# MCU.net
KiCad netlist of a schematic drawn in Altium Designer
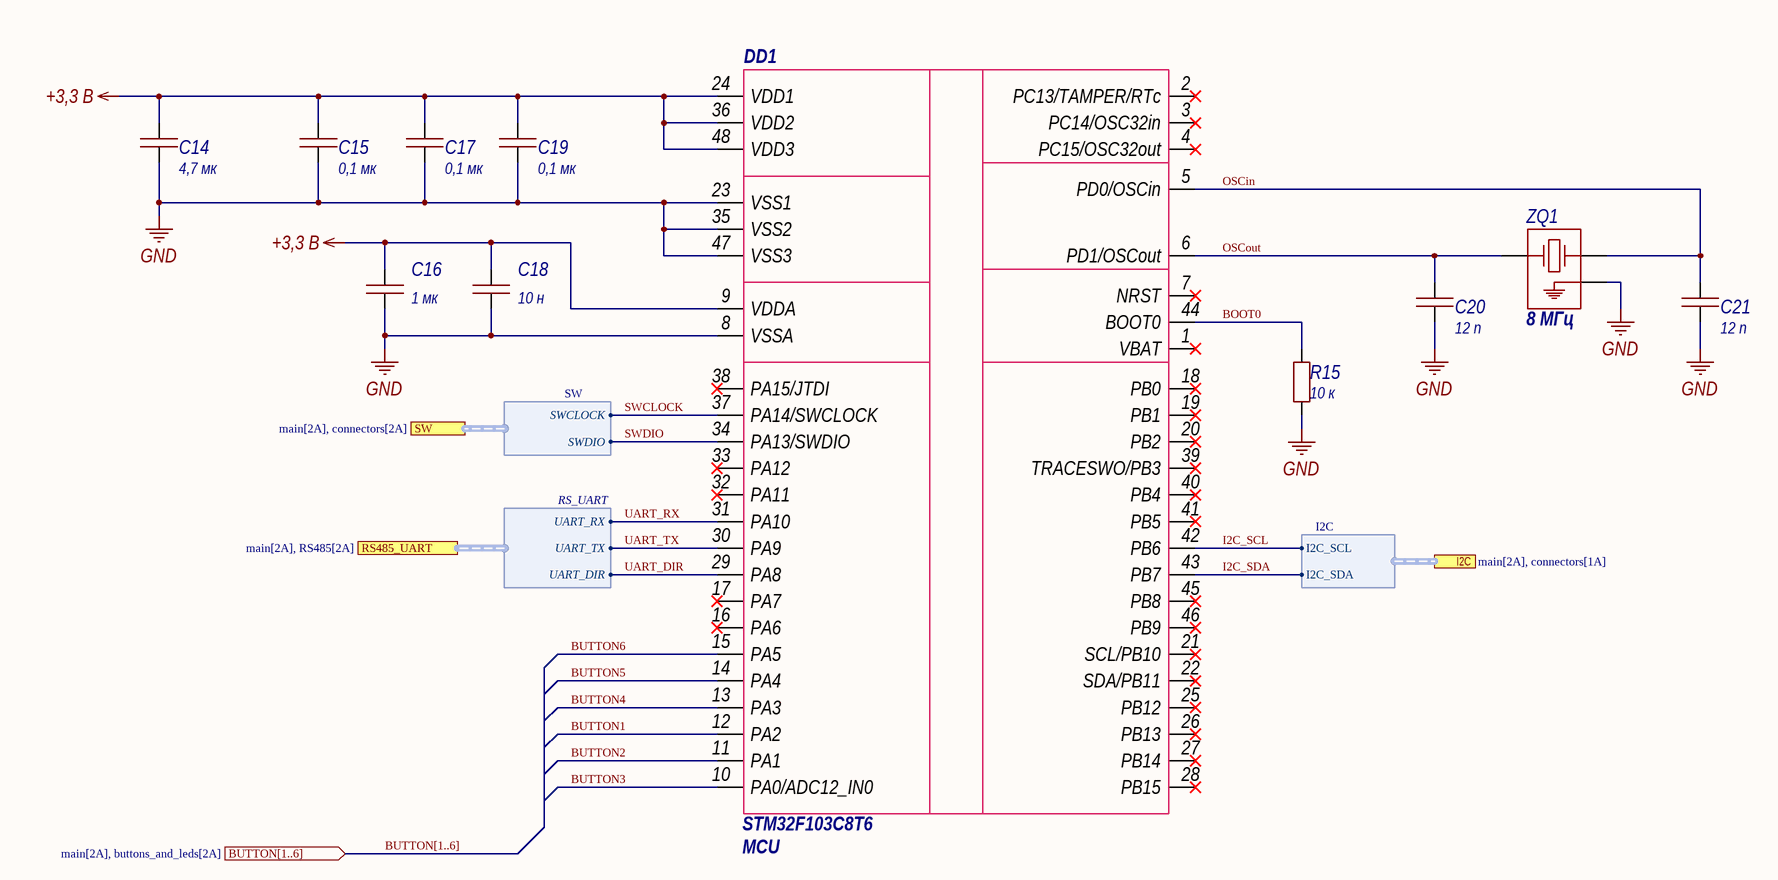
[diagram p0: MCU.SchDoc]

(export (version "E")
  (design (tool "Eeschema 10.0.6"))
  (components
    (comp (ref "C14")
      (value "4,7 мк")
      (footprint "1206C")
      (description "Конденсатор 1206C ёмкостью 4,7 мк 10%, 50 В, X7R")
      (fields (field (name "PART NUMBER") "Capacitor_4,7u_10_50V_X7R_1206C") (field (name "TOLERANCE") "10%"))
      (libsource (lib "Hydrolib") (part "Capacitor"))
    )
    (comp (ref "C15")
      (value "0,1 мк")
      (footprint "0603C")
      (description "Конденсатор 0603C ёмкостью 0,1 мк 10%, 50 В, X7R")
      (fields (field (name "PART NUMBER") "Capacitor_0,1u_10_50V_X7R_0603C") (field (name "TOLERANCE") "10%"))
      (libsource (lib "Hydrolib") (part "Capacitor"))
    )
    (comp (ref "C16")
      (value "1 мк")
      (footprint "0603C")
      (description "Конденсатор 0603C ёмкостью 1 мк 10%, 50 В, X7R")
      (fields (field (name "PART NUMBER") "Capacitor_1u_10_50V_X7R_0603C") (field (name "TOLERANCE") "10%"))
      (libsource (lib "Hydrolib") (part "Capacitor"))
    )
    (comp (ref "C17")
      (value "0,1 мк")
      (footprint "0603C")
      (description "Конденсатор 0603C ёмкостью 0,1 мк 10%, 50 В, X7R")
      (fields (field (name "PART NUMBER") "Capacitor_0,1u_10_50V_X7R_0603C") (field (name "TOLERANCE") "10%"))
      (libsource (lib "Hydrolib") (part "Capacitor"))
    )
    (comp (ref "C18")
      (value "10 н")
      (footprint "0603C")
      (description "Конденсатор 0603C ёмкостью 10 н 10%, 50 В, X7R")
      (fields (field (name "PART NUMBER") "Capacitor_10n_10_50V_X7R_0603C") (field (name "TOLERANCE") "10%"))
      (libsource (lib "Hydrolib") (part "Capacitor"))
    )
    (comp (ref "C19")
      (value "0,1 мк")
      (footprint "0603C")
      (description "Конденсатор 0603C ёмкостью 0,1 мк 10%, 50 В, X7R")
      (fields (field (name "PART NUMBER") "Capacitor_0,1u_10_50V_X7R_0603C") (field (name "TOLERANCE") "10%"))
      (libsource (lib "Hydrolib") (part "Capacitor"))
    )
    (comp (ref "C20")
      (value "12 п")
      (footprint "0603C")
      (description "Конденсатор 12п")
      (fields (field (name "PART NUMBER") "Capacitor"))
      (libsource (lib "Hydrolib") (part "Capacitor"))
    )
    (comp (ref "C21")
      (value "12 п")
      (footprint "0603C")
      (description "Конденсатор 12п")
      (fields (field (name "PART NUMBER") "Capacitor"))
      (libsource (lib "Hydrolib") (part "Capacitor"))
    )
    (comp (ref "DD1")
      (value "STM32F103C8T6")
      (footprint "LQFP48")
      (description "Микроконтроллер")
      (fields (field (name "MANUFACTURER") "ST Microelectronics") (field (name "VALUE1") "MCU"))
      (libsource (lib "Hydrolib") (part "STM32F103C8T6"))
    )
    (comp (ref "R15")
      (value "10 к")
      (footprint "0603R")
      (description "Резистор номиналом 10 кОм 1%")
      (fields (field (name "PART NUMBER") "Resistor_10k_1_0603") (field (name "TOLERANCE") "1%"))
      (libsource (lib "Hydrolib") (part "Resistor"))
    )
    (comp (ref "ZQ1")
      (value "8 МГц")
      (footprint "QSMD3.2x2.5")
      (description "Кварцевый резонатор с входом земли")
      (fields (field (name "PART NUMBER") "XTAL_GND"))
      (libsource (lib "Hydrolib") (part "XTAL_GND"))
    )
  )
  (nets
    (net (code "4") (name "+3,3 В") (class "Default")
      (node (ref "C14") (pin "2") (pinfunction "2_2") (pintype "passive"))
      (node (ref "C15") (pin "2") (pinfunction "2_2") (pintype "passive"))
      (node (ref "C16") (pin "2") (pinfunction "2_2") (pintype "passive"))
      (node (ref "C17") (pin "2") (pinfunction "2_2") (pintype "passive"))
      (node (ref "C18") (pin "2") (pinfunction "2_2") (pintype "passive"))
      (node (ref "C19") (pin "2") (pinfunction "2_2") (pintype "passive"))
      (node (ref "DD1") (pin "24") (pinfunction "VDD1_24") (pintype "passive"))
      (node (ref "DD1") (pin "36") (pinfunction "VDD2_36") (pintype "passive"))
      (node (ref "DD1") (pin "48") (pinfunction "VDD3_48") (pintype "passive"))
      (node (ref "DD1") (pin "9") (pinfunction "VDDA_9") (pintype "passive"))
    )
    (net (code "5") (name "/BOOT0") (class "Default")
      (node (ref "DD1") (pin "44") (pinfunction "BOOT0_44") (pintype "passive"))
      (node (ref "R15") (pin "2") (pinfunction "2_2") (pintype "passive"))
    )
    (net (code "6") (name "/BUTTON1") (class "Default")
      (node (ref "DD1") (pin "12") (pinfunction "PA2_12") (pintype "passive"))
    )
    (net (code "7") (name "/BUTTON2") (class "Default")
      (node (ref "DD1") (pin "11") (pinfunction "PA1_11") (pintype "passive"))
    )
    (net (code "8") (name "/BUTTON3") (class "Default")
      (node (ref "DD1") (pin "10") (pinfunction "PA0/ADC12_IN0_10") (pintype "passive"))
    )
    (net (code "9") (name "/BUTTON4") (class "Default")
      (node (ref "DD1") (pin "13") (pinfunction "PA3_13") (pintype "passive"))
    )
    (net (code "10") (name "/BUTTON5") (class "Default")
      (node (ref "DD1") (pin "14") (pinfunction "PA4_14") (pintype "passive"))
    )
    (net (code "11") (name "/BUTTON6") (class "Default")
      (node (ref "DD1") (pin "15") (pinfunction "PA5_15") (pintype "passive"))
    )
    (net (code "13") (name "/I2C_SCL") (class "Default")
      (node (ref "DD1") (pin "42") (pinfunction "PB6_42") (pintype "passive"))
    )
    (net (code "14") (name "/I2C_SDA") (class "Default")
      (node (ref "DD1") (pin "43") (pinfunction "PB7_43") (pintype "passive"))
    )
    (net (code "15") (name "/OSCin") (class "Default")
      (node (ref "C21") (pin "2") (pinfunction "2_2") (pintype "passive"))
      (node (ref "DD1") (pin "5") (pinfunction "PD0/OSCin_5") (pintype "passive"))
      (node (ref "ZQ1") (pin "2") (pinfunction "2_2") (pintype "passive"))
    )
    (net (code "16") (name "/OSCout") (class "Default")
      (node (ref "C20") (pin "2") (pinfunction "2_2") (pintype "passive"))
      (node (ref "DD1") (pin "6") (pinfunction "PD1/OSCout_6") (pintype "passive"))
      (node (ref "ZQ1") (pin "1") (pinfunction "1_1") (pintype "passive"))
    )
    (net (code "17") (name "/SWCLOCK") (class "Default")
      (node (ref "DD1") (pin "37") (pinfunction "PA14/SWCLOCK_37") (pintype "passive"))
    )
    (net (code "18") (name "/SWDIO") (class "Default")
      (node (ref "DD1") (pin "34") (pinfunction "PA13/SWDIO_34") (pintype "passive"))
    )
    (net (code "19") (name "/UART_DIR") (class "Default")
      (node (ref "DD1") (pin "29") (pinfunction "PA8_29") (pintype "passive"))
    )
    (net (code "20") (name "/UART_RX") (class "Default")
      (node (ref "DD1") (pin "31") (pinfunction "PA10_31") (pintype "passive"))
    )
    (net (code "21") (name "/UART_TX") (class "Default")
      (node (ref "DD1") (pin "30") (pinfunction "PA9_30") (pintype "passive"))
    )
    (net (code "25") (name "GND") (class "Default")
      (node (ref "C14") (pin "1") (pinfunction "1_1") (pintype "passive"))
      (node (ref "C15") (pin "1") (pinfunction "1_1") (pintype "passive"))
      (node (ref "C16") (pin "1") (pinfunction "1_1") (pintype "passive"))
      (node (ref "C17") (pin "1") (pinfunction "1_1") (pintype "passive"))
      (node (ref "C18") (pin "1") (pinfunction "1_1") (pintype "passive"))
      (node (ref "C19") (pin "1") (pinfunction "1_1") (pintype "passive"))
      (node (ref "C20") (pin "1") (pinfunction "1_1") (pintype "passive"))
      (node (ref "C21") (pin "1") (pinfunction "1_1") (pintype "passive"))
      (node (ref "DD1") (pin "23") (pinfunction "VSS1_23") (pintype "passive"))
      (node (ref "DD1") (pin "35") (pinfunction "VSS2_35") (pintype "passive"))
      (node (ref "DD1") (pin "47") (pinfunction "VSS3_47") (pintype "passive"))
      (node (ref "DD1") (pin "8") (pinfunction "VSSA_8") (pintype "passive"))
      (node (ref "R15") (pin "1") (pinfunction "1_1") (pintype "passive"))
      (node (ref "ZQ1") (pin "3") (pinfunction "3_3") (pintype "passive"))
    )
    (net (code "26") (name "unconnected-(DD1-NRST-Pad7)") (class "Default")
      (node (ref "DD1") (pin "7") (pinfunction "NRST_7") (pintype "passive+no_connect"))
    )
    (net (code "27") (name "unconnected-(DD1-PA6-Pad16)") (class "Default")
      (node (ref "DD1") (pin "16") (pinfunction "PA6_16") (pintype "passive+no_connect"))
    )
    (net (code "28") (name "unconnected-(DD1-PA7-Pad17)") (class "Default")
      (node (ref "DD1") (pin "17") (pinfunction "PA7_17") (pintype "passive+no_connect"))
    )
    (net (code "29") (name "unconnected-(DD1-PA11-Pad32)") (class "Default")
      (node (ref "DD1") (pin "32") (pinfunction "PA11_32") (pintype "passive+no_connect"))
    )
    (net (code "30") (name "unconnected-(DD1-PA12-Pad33)") (class "Default")
      (node (ref "DD1") (pin "33") (pinfunction "PA12_33") (pintype "passive+no_connect"))
    )
    (net (code "31") (name "unconnected-(DD1-PA15{slash}JTDI-Pad38)") (class "Default")
      (node (ref "DD1") (pin "38") (pinfunction "PA15/JTDI_38") (pintype "passive+no_connect"))
    )
    (net (code "32") (name "unconnected-(DD1-PB0-Pad18)") (class "Default")
      (node (ref "DD1") (pin "18") (pinfunction "PB0_18") (pintype "passive+no_connect"))
    )
    (net (code "33") (name "unconnected-(DD1-PB1-Pad19)") (class "Default")
      (node (ref "DD1") (pin "19") (pinfunction "PB1_19") (pintype "passive+no_connect"))
    )
    (net (code "34") (name "unconnected-(DD1-PB2-Pad20)") (class "Default")
      (node (ref "DD1") (pin "20") (pinfunction "PB2_20") (pintype "passive+no_connect"))
    )
    (net (code "35") (name "unconnected-(DD1-PB4-Pad40)") (class "Default")
      (node (ref "DD1") (pin "40") (pinfunction "PB4_40") (pintype "passive+no_connect"))
    )
    (net (code "36") (name "unconnected-(DD1-PB5-Pad41)") (class "Default")
      (node (ref "DD1") (pin "41") (pinfunction "PB5_41") (pintype "passive+no_connect"))
    )
    (net (code "37") (name "unconnected-(DD1-PB8-Pad45)") (class "Default")
      (node (ref "DD1") (pin "45") (pinfunction "PB8_45") (pintype "passive+no_connect"))
    )
    (net (code "38") (name "unconnected-(DD1-PB9-Pad46)") (class "Default")
      (node (ref "DD1") (pin "46") (pinfunction "PB9_46") (pintype "passive+no_connect"))
    )
    (net (code "39") (name "unconnected-(DD1-PB12-Pad25)") (class "Default")
      (node (ref "DD1") (pin "25") (pinfunction "PB12_25") (pintype "passive+no_connect"))
    )
    (net (code "40") (name "unconnected-(DD1-PB13-Pad26)") (class "Default")
      (node (ref "DD1") (pin "26") (pinfunction "PB13_26") (pintype "passive+no_connect"))
    )
    (net (code "41") (name "unconnected-(DD1-PB14-Pad27)") (class "Default")
      (node (ref "DD1") (pin "27") (pinfunction "PB14_27") (pintype "passive+no_connect"))
    )
    (net (code "42") (name "unconnected-(DD1-PB15-Pad28)") (class "Default")
      (node (ref "DD1") (pin "28") (pinfunction "PB15_28") (pintype "passive+no_connect"))
    )
    (net (code "43") (name "unconnected-(DD1-PC13{slash}TAMPER{slash}RTc-Pad2)") (class "Default")
      (node (ref "DD1") (pin "2") (pinfunction "PC13/TAMPER/RTc_2") (pintype "passive+no_connect"))
    )
    (net (code "44") (name "unconnected-(DD1-PC14{slash}OSC32in-Pad3)") (class "Default")
      (node (ref "DD1") (pin "3") (pinfunction "PC14/OSC32in_3") (pintype "passive+no_connect"))
    )
    (net (code "45") (name "unconnected-(DD1-PC15{slash}OSC32out-Pad4)") (class "Default")
      (node (ref "DD1") (pin "4") (pinfunction "PC15/OSC32out_4") (pintype "passive+no_connect"))
    )
    (net (code "46") (name "unconnected-(DD1-SCL{slash}PB10-Pad21)") (class "Default")
      (node (ref "DD1") (pin "21") (pinfunction "SCL/PB10_21") (pintype "passive+no_connect"))
    )
    (net (code "47") (name "unconnected-(DD1-SDA{slash}PB11-Pad22)") (class "Default")
      (node (ref "DD1") (pin "22") (pinfunction "SDA/PB11_22") (pintype "passive+no_connect"))
    )
    (net (code "48") (name "unconnected-(DD1-TRACESWO{slash}PB3-Pad39)") (class "Default")
      (node (ref "DD1") (pin "39") (pinfunction "TRACESWO/PB3_39") (pintype "passive+no_connect"))
    )
    (net (code "49") (name "unconnected-(DD1-VBAT-Pad1)") (class "Default")
      (node (ref "DD1") (pin "1") (pinfunction "VBAT_1") (pintype "passive+no_connect"))
    )
  )
)
